# LR21_Dash.net
KiCad netlist of a schematic drawn in EAGLE
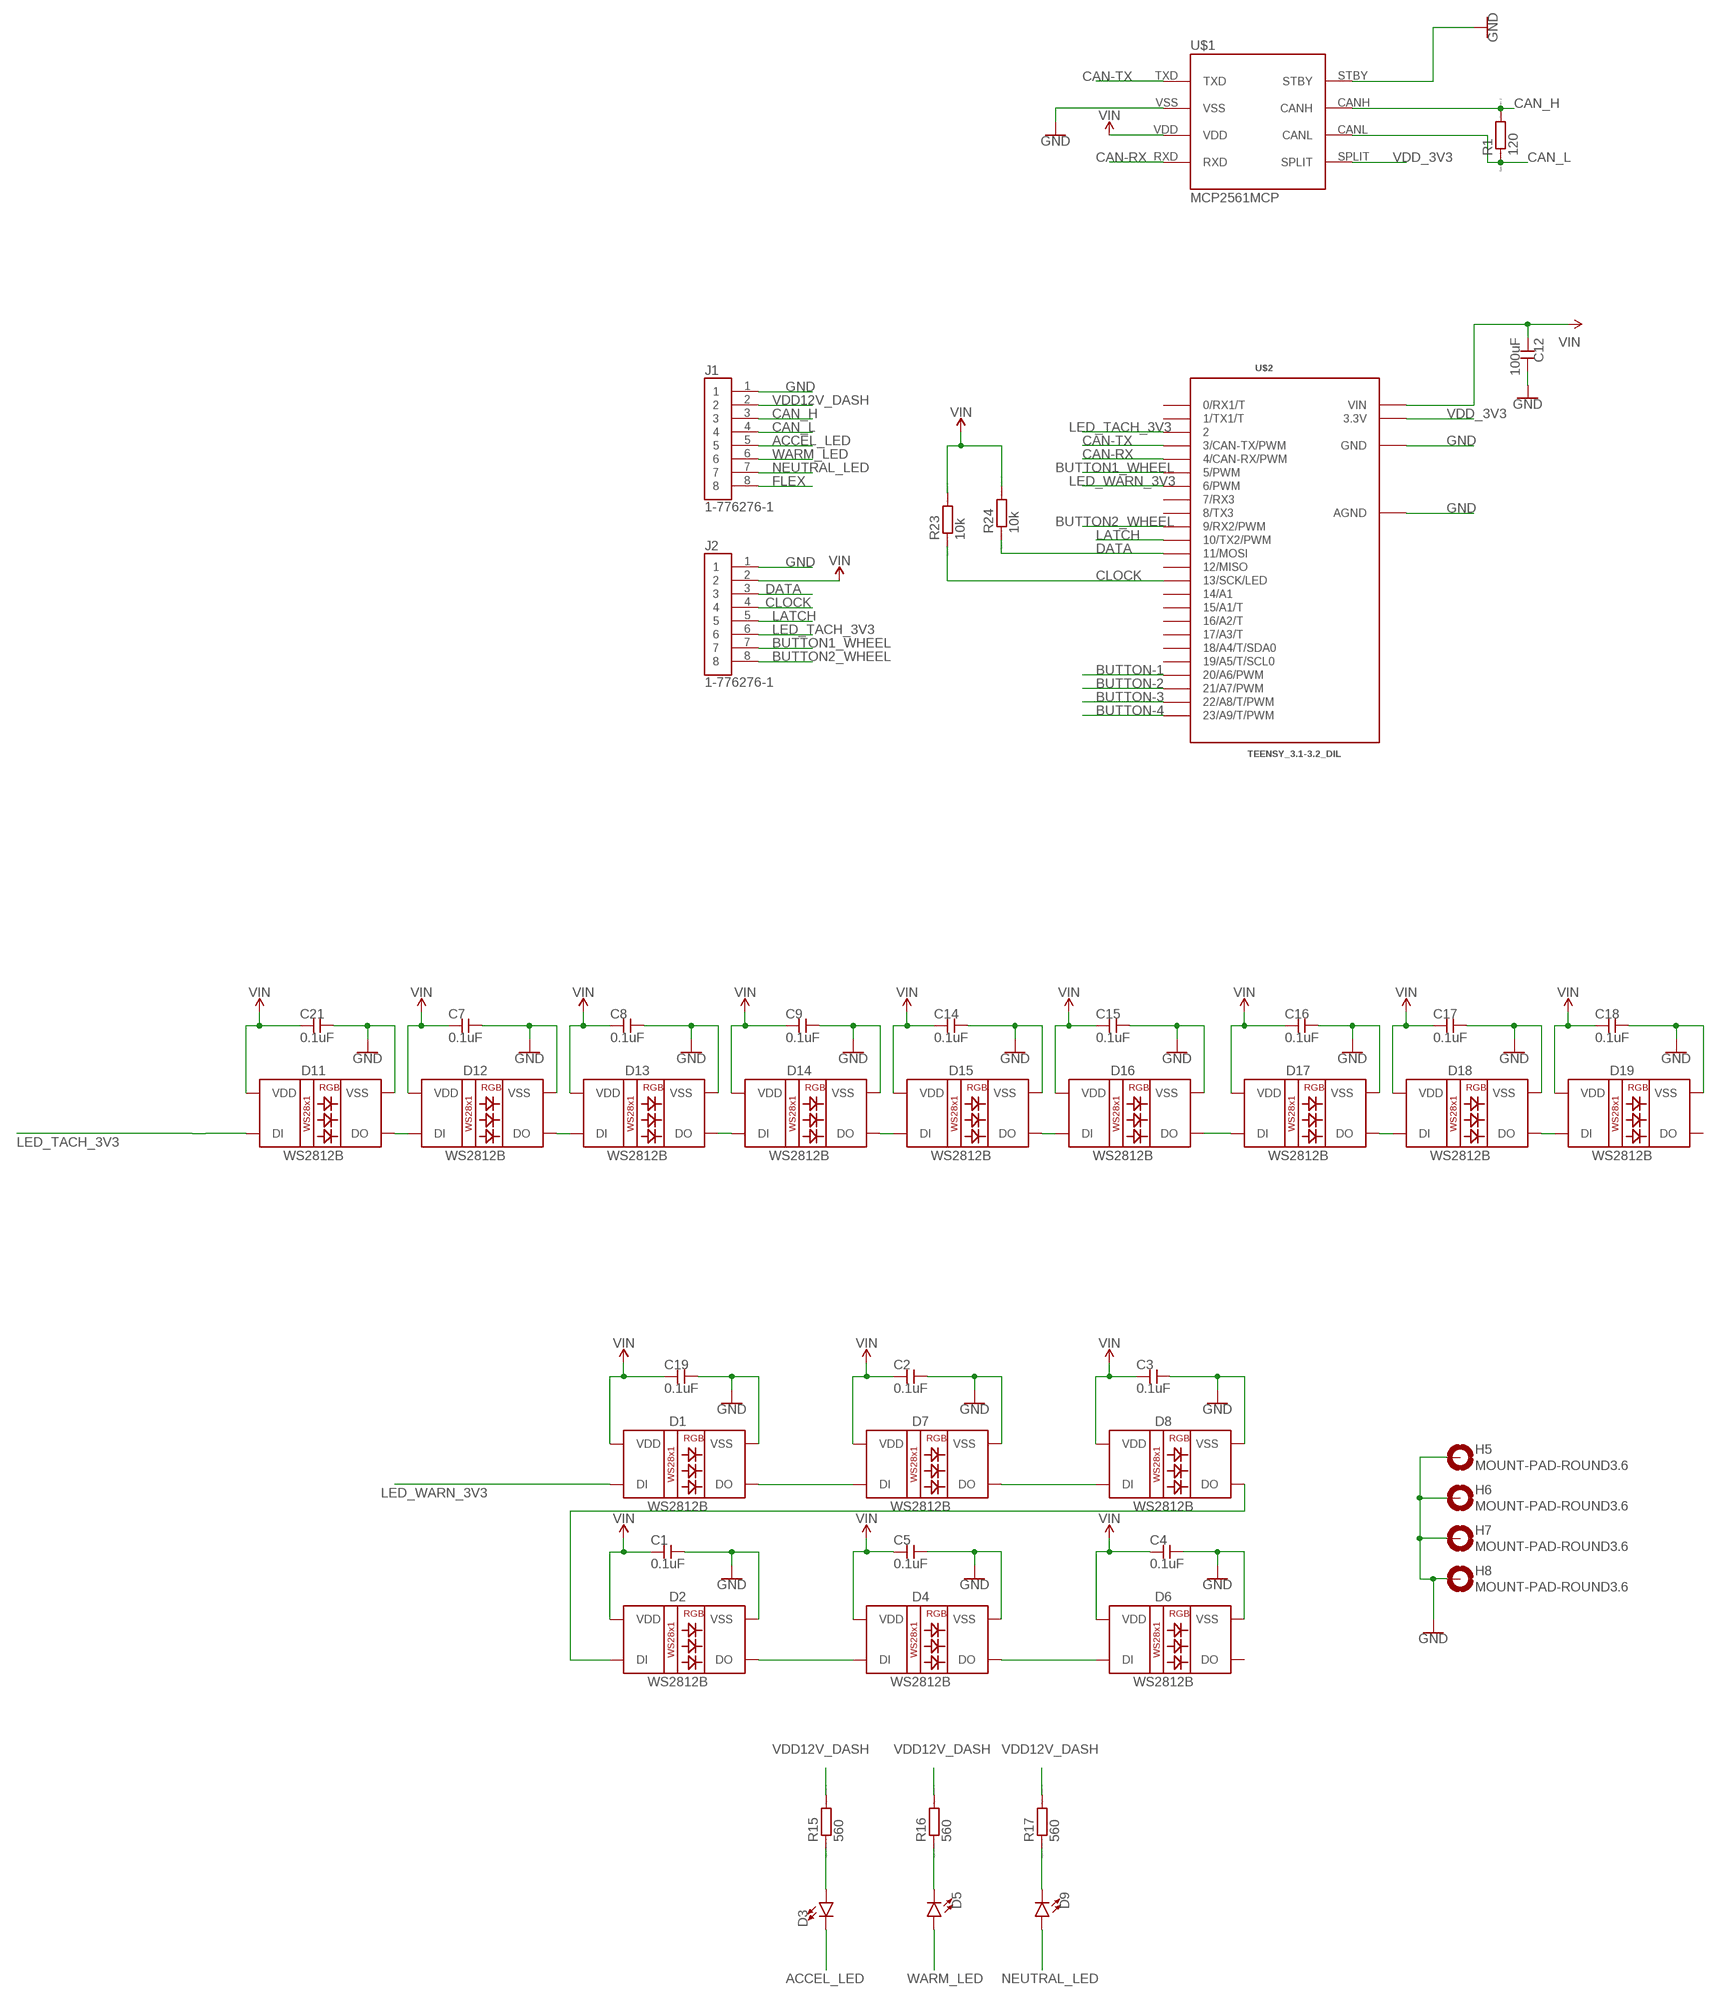
[diagram p0: schematic, sheet 1, part 1 of 2]
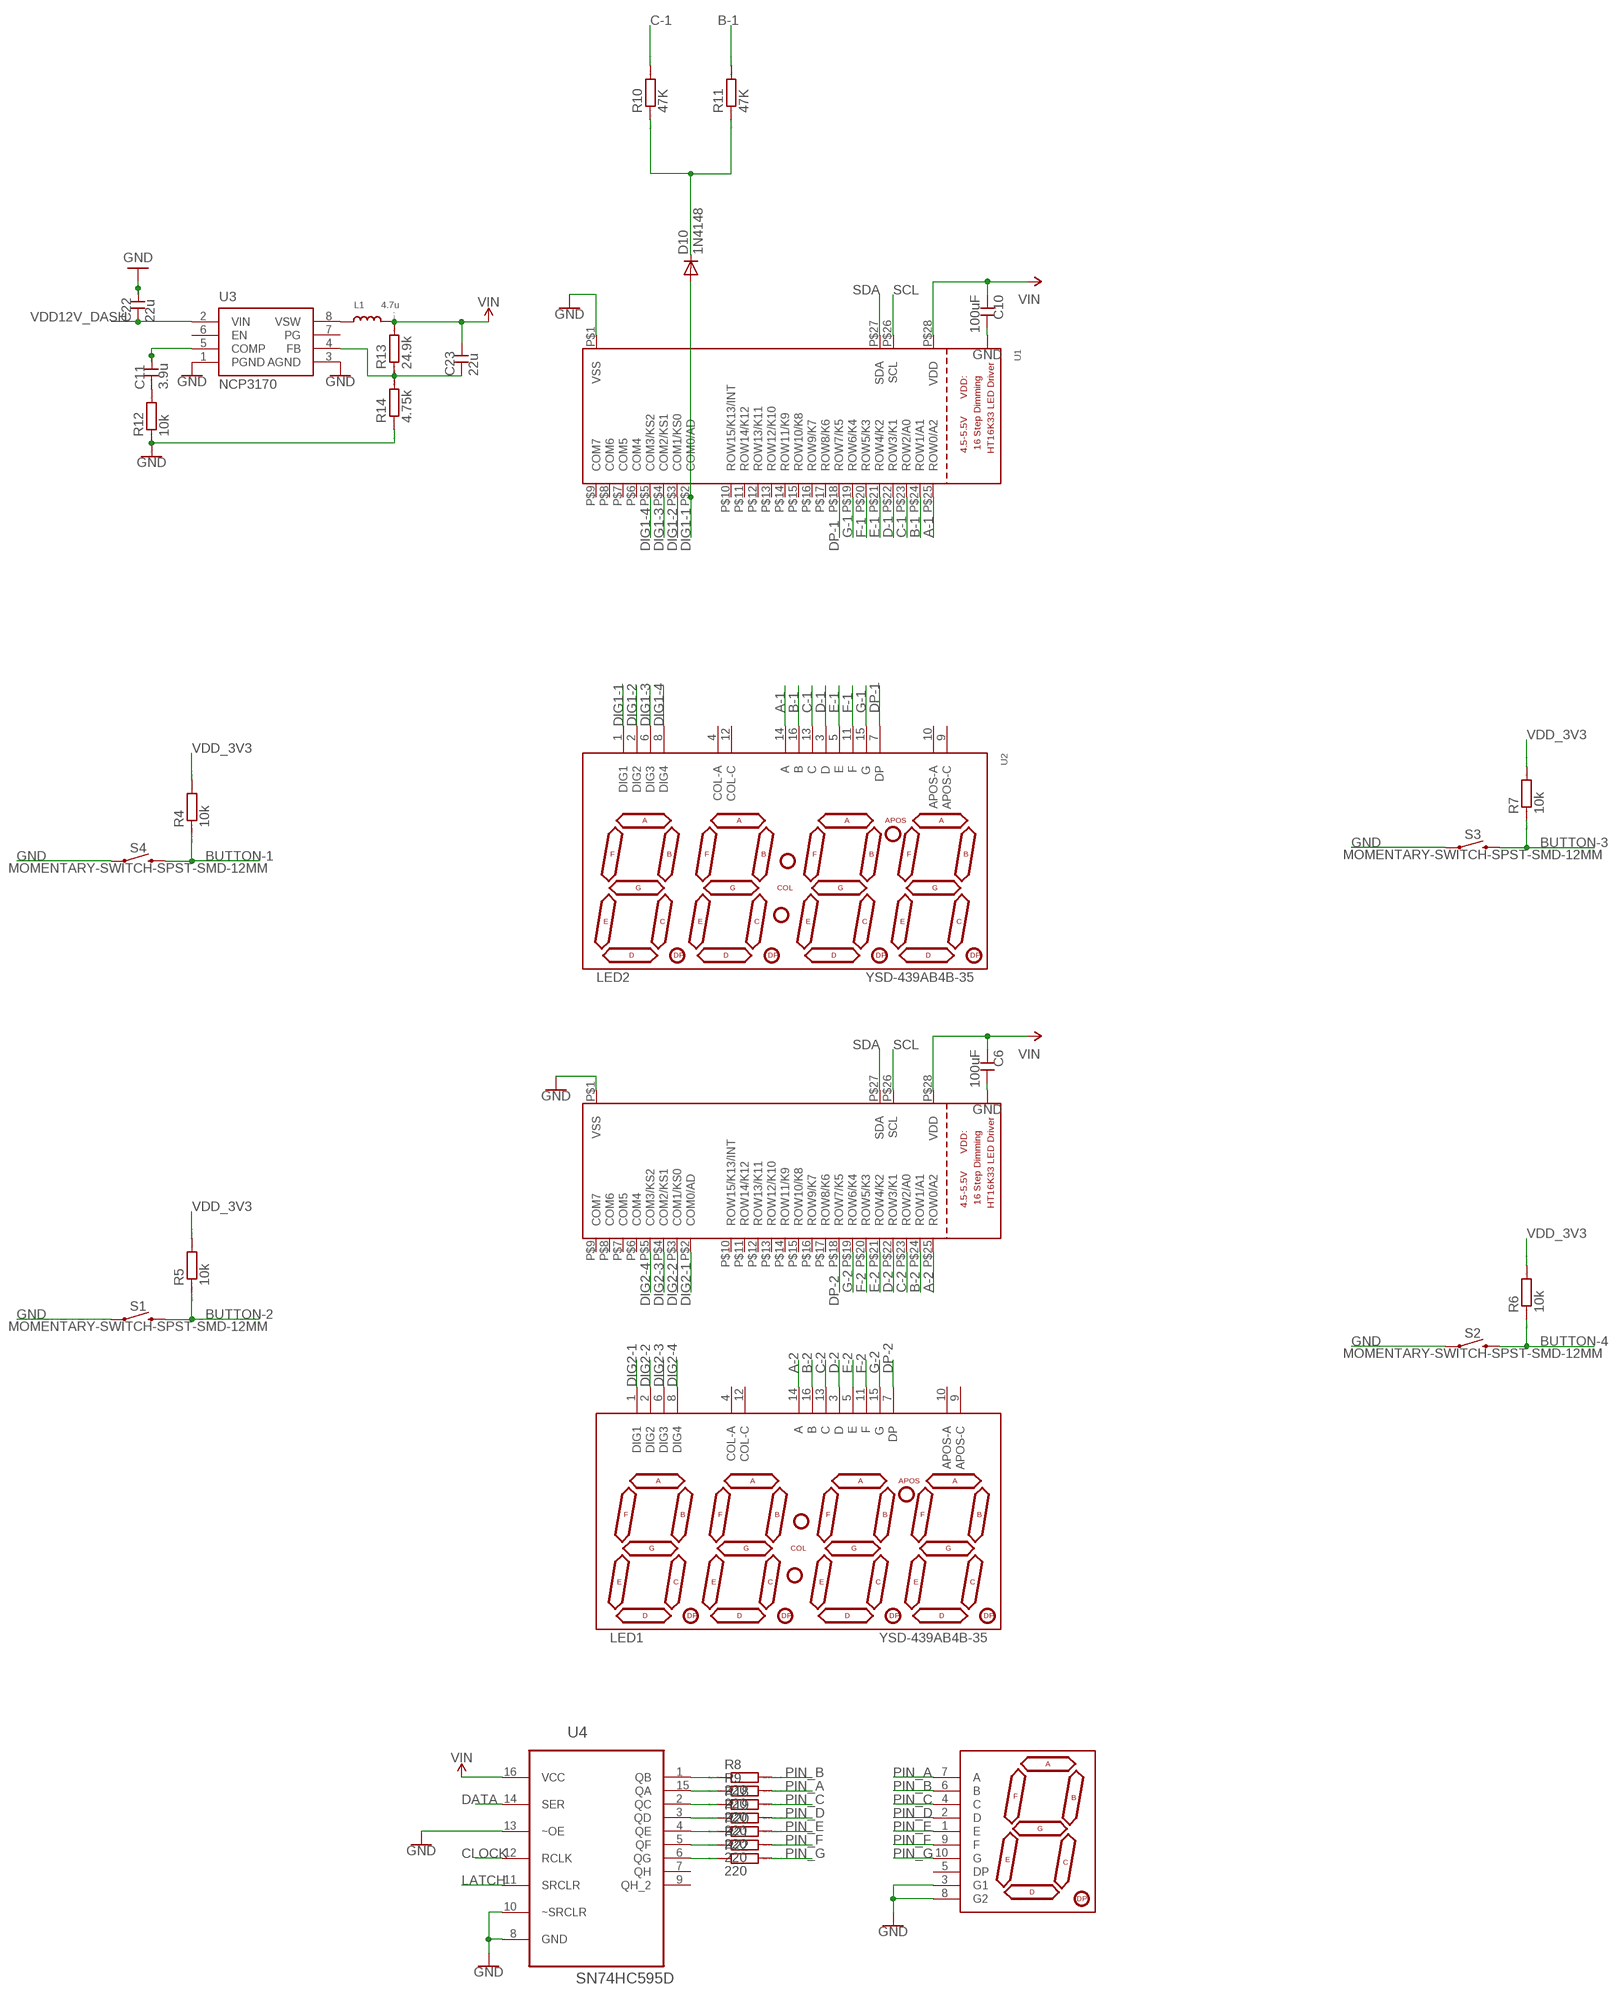
[diagram p1: schematic, sheet 1, part 2 of 2]

(export (version "E")
  (design (tool "Eeschema 10.0.6"))
  (components
    (comp (ref "C1")
      (value "0.1uF")
      (footprint "eagle-import:1005")
      (libsource (lib "eagle-import") (part "CAP-1005"))
    )
    (comp (ref "C2")
      (value "0.1uF")
      (footprint "eagle-import:1005")
      (libsource (lib "eagle-import") (part "CAP-1005"))
    )
    (comp (ref "C3")
      (value "0.1uF")
      (footprint "eagle-import:1005")
      (libsource (lib "eagle-import") (part "CAP-1005"))
    )
    (comp (ref "C4")
      (value "0.1uF")
      (footprint "eagle-import:1005")
      (libsource (lib "eagle-import") (part "CAP-1005"))
    )
    (comp (ref "C5")
      (value "0.1uF")
      (footprint "eagle-import:1005")
      (libsource (lib "eagle-import") (part "CAP-1005"))
    )
    (comp (ref "C6")
      (value "100uF")
      (footprint "eagle-import:1005")
      (libsource (lib "eagle-import") (part "CAP-1005"))
    )
    (comp (ref "C7")
      (value "0.1uF")
      (footprint "eagle-import:1005")
      (libsource (lib "eagle-import") (part "CAP-1005"))
    )
    (comp (ref "C8")
      (value "0.1uF")
      (footprint "eagle-import:1005")
      (libsource (lib "eagle-import") (part "CAP-1005"))
    )
    (comp (ref "C9")
      (value "0.1uF")
      (footprint "eagle-import:1005")
      (libsource (lib "eagle-import") (part "CAP-1005"))
    )
    (comp (ref "C10")
      (value "100uF")
      (footprint "eagle-import:1005")
      (libsource (lib "eagle-import") (part "CAP-1005"))
    )
    (comp (ref "C11")
      (value "3.9u")
      (footprint "eagle-import:1005")
      (libsource (lib "eagle-import") (part "CAP-1005"))
    )
    (comp (ref "C12")
      (value "100uF")
      (footprint "eagle-import:1005")
      (libsource (lib "eagle-import") (part "CAP-1005"))
    )
    (comp (ref "C14")
      (value "0.1uF")
      (footprint "eagle-import:1005")
      (libsource (lib "eagle-import") (part "CAP-1005"))
    )
    (comp (ref "C15")
      (value "0.1uF")
      (footprint "eagle-import:1005")
      (libsource (lib "eagle-import") (part "CAP-1005"))
    )
    (comp (ref "C16")
      (value "0.1uF")
      (footprint "eagle-import:1005")
      (libsource (lib "eagle-import") (part "CAP-1005"))
    )
    (comp (ref "C17")
      (value "0.1uF")
      (footprint "eagle-import:1005")
      (libsource (lib "eagle-import") (part "CAP-1005"))
    )
    (comp (ref "C18")
      (value "0.1uF")
      (footprint "eagle-import:1005")
      (libsource (lib "eagle-import") (part "CAP-1005"))
    )
    (comp (ref "C19")
      (value "0.1uF")
      (footprint "eagle-import:1005")
      (libsource (lib "eagle-import") (part "CAP-1005"))
    )
    (comp (ref "C21")
      (value "0.1uF")
      (footprint "eagle-import:1005")
      (libsource (lib "eagle-import") (part "CAP-1005"))
    )
    (comp (ref "C22")
      (value "22u")
      (footprint "eagle-import:1005")
      (libsource (lib "eagle-import") (part "CAP-1005"))
    )
    (comp (ref "C23")
      (value "22u")
      (footprint "eagle-import:1005")
      (libsource (lib "eagle-import") (part "CAP-1005"))
    )
    (comp (ref "D1")
      (value "WS2812B")
      (footprint "eagle-import:WS2812B")
      (libsource (lib "eagle-import") (part "WS2812B"))
    )
    (comp (ref "D2")
      (value "WS2812B")
      (footprint "eagle-import:WS2812B")
      (libsource (lib "eagle-import") (part "WS2812B"))
    )
    (comp (ref "D3")
      (value "LED5MM")
      (footprint "eagle-import:LED_5MM")
      (libsource (lib "eagle-import") (part "LED5MM"))
    )
    (comp (ref "D4")
      (value "WS2812B")
      (footprint "eagle-import:WS2812B")
      (libsource (lib "eagle-import") (part "WS2812B"))
    )
    (comp (ref "D5")
      (value "LED5MM")
      (footprint "eagle-import:LED_5MM")
      (libsource (lib "eagle-import") (part "LED5MM"))
    )
    (comp (ref "D6")
      (value "WS2812B")
      (footprint "eagle-import:WS2812B")
      (libsource (lib "eagle-import") (part "WS2812B"))
    )
    (comp (ref "D7")
      (value "WS2812B")
      (footprint "eagle-import:WS2812B")
      (libsource (lib "eagle-import") (part "WS2812B"))
    )
    (comp (ref "D8")
      (value "WS2812B")
      (footprint "eagle-import:WS2812B")
      (libsource (lib "eagle-import") (part "WS2812B"))
    )
    (comp (ref "D9")
      (value "LED5MM")
      (footprint "eagle-import:LED_5MM")
      (libsource (lib "eagle-import") (part "LED5MM"))
    )
    (comp (ref "D10")
      (value "1N4148")
      (footprint "eagle-import:DO35-10")
      (libsource (lib "eagle-import") (part "1N4148"))
    )
    (comp (ref "D11")
      (value "WS2812B")
      (footprint "eagle-import:WS2812B")
      (libsource (lib "eagle-import") (part "WS2812B"))
    )
    (comp (ref "D12")
      (value "WS2812B")
      (footprint "eagle-import:WS2812B")
      (libsource (lib "eagle-import") (part "WS2812B"))
    )
    (comp (ref "D13")
      (value "WS2812B")
      (footprint "eagle-import:WS2812B")
      (libsource (lib "eagle-import") (part "WS2812B"))
    )
    (comp (ref "D14")
      (value "WS2812B")
      (footprint "eagle-import:WS2812B")
      (libsource (lib "eagle-import") (part "WS2812B"))
    )
    (comp (ref "D15")
      (value "WS2812B")
      (footprint "eagle-import:WS2812B")
      (libsource (lib "eagle-import") (part "WS2812B"))
    )
    (comp (ref "D16")
      (value "WS2812B")
      (footprint "eagle-import:WS2812B")
      (libsource (lib "eagle-import") (part "WS2812B"))
    )
    (comp (ref "D17")
      (value "WS2812B")
      (footprint "eagle-import:WS2812B")
      (libsource (lib "eagle-import") (part "WS2812B"))
    )
    (comp (ref "D18")
      (value "WS2812B")
      (footprint "eagle-import:WS2812B")
      (libsource (lib "eagle-import") (part "WS2812B"))
    )
    (comp (ref "D19")
      (value "WS2812B")
      (footprint "eagle-import:WS2812B")
      (libsource (lib "eagle-import") (part "WS2812B"))
    )
    (comp (ref "H5")
      (value "MOUNT-PAD-ROUND3.6")
      (footprint "eagle-import:3,6-PAD")
      (libsource (lib "eagle-import") (part "MOUNT-PAD-ROUND3.6"))
    )
    (comp (ref "H6")
      (value "MOUNT-PAD-ROUND3.6")
      (footprint "eagle-import:3,6-PAD")
      (libsource (lib "eagle-import") (part "MOUNT-PAD-ROUND3.6"))
    )
    (comp (ref "H7")
      (value "MOUNT-PAD-ROUND3.6")
      (footprint "eagle-import:3,6-PAD")
      (libsource (lib "eagle-import") (part "MOUNT-PAD-ROUND3.6"))
    )
    (comp (ref "H8")
      (value "MOUNT-PAD-ROUND3.6")
      (footprint "eagle-import:3,6-PAD")
      (libsource (lib "eagle-import") (part "MOUNT-PAD-ROUND3.6"))
    )
    (comp (ref "J1")
      (value "1-776276-1")
      (footprint "eagle-import:TE_1-776276-1")
      (fields (field (name "MANUFACTURER") "TE Connectivity"))
      (libsource (lib "eagle-import") (part "1-776276-1"))
    )
    (comp (ref "J2")
      (value "1-776276-1")
      (footprint "eagle-import:TE_1-776276-1")
      (fields (field (name "MANUFACTURER") "TE Connectivity"))
      (libsource (lib "eagle-import") (part "1-776276-1"))
    )
    (comp (ref "L1")
      (value "4.7u")
      (footprint "eagle-import:INDUCTOR_1007")
      (libsource (lib "eagle-import") (part "INDUCTOR"))
    )
    (comp (ref "LED1")
      (value "YSD-439AB4B-35")
      (footprint "eagle-import:7-SEGMENT-4DIGIT-YOUNGSUN")
      (libsource (lib "eagle-import") (part "7-SEGMENT-4DIGIT-10MM-BLUE"))
    )
    (comp (ref "LED2")
      (value "YSD-439AB4B-35")
      (footprint "eagle-import:7-SEGMENT-4DIGIT-YOUNGSUN")
      (libsource (lib "eagle-import") (part "7-SEGMENT-4DIGIT-10MM-BLUE"))
    )
    (comp (ref "R1")
      (value "120")
      (footprint "eagle-import:R0805")
      (libsource (lib "eagle-import") (part "R"))
    )
    (comp (ref "R4")
      (value "10k")
      (footprint "eagle-import:R0805")
      (libsource (lib "eagle-import") (part "R"))
    )
    (comp (ref "R5")
      (value "10k")
      (footprint "eagle-import:R0805")
      (libsource (lib "eagle-import") (part "R"))
    )
    (comp (ref "R6")
      (value "10k")
      (footprint "eagle-import:R0805")
      (libsource (lib "eagle-import") (part "R"))
    )
    (comp (ref "R7")
      (value "10k")
      (footprint "eagle-import:R0805")
      (libsource (lib "eagle-import") (part "R"))
    )
    (comp (ref "R8")
      (value "220")
      (footprint "eagle-import:R0805")
      (libsource (lib "eagle-import") (part "R"))
    )
    (comp (ref "R9")
      (value "220")
      (footprint "eagle-import:R0805")
      (libsource (lib "eagle-import") (part "R"))
    )
    (comp (ref "R10")
      (value "47K")
      (footprint "eagle-import:R0805")
      (libsource (lib "eagle-import") (part "R"))
    )
    (comp (ref "R11")
      (value "47K")
      (footprint "eagle-import:R0805")
      (libsource (lib "eagle-import") (part "R"))
    )
    (comp (ref "R12")
      (value "10k")
      (footprint "eagle-import:R0805")
      (libsource (lib "eagle-import") (part "R"))
    )
    (comp (ref "R13")
      (value "24.9k")
      (footprint "eagle-import:R0805")
      (libsource (lib "eagle-import") (part "R"))
    )
    (comp (ref "R14")
      (value "4.75k")
      (footprint "eagle-import:R0805")
      (libsource (lib "eagle-import") (part "R"))
    )
    (comp (ref "R15")
      (value "560")
      (footprint "eagle-import:R0805")
      (libsource (lib "eagle-import") (part "R"))
    )
    (comp (ref "R16")
      (value "560")
      (footprint "eagle-import:R0805")
      (libsource (lib "eagle-import") (part "R"))
    )
    (comp (ref "R17")
      (value "560")
      (footprint "eagle-import:R0805")
      (libsource (lib "eagle-import") (part "R"))
    )
    (comp (ref "R18")
      (value "220")
      (footprint "eagle-import:R0805")
      (libsource (lib "eagle-import") (part "R"))
    )
    (comp (ref "R19")
      (value "220")
      (footprint "eagle-import:R0805")
      (libsource (lib "eagle-import") (part "R"))
    )
    (comp (ref "R20")
      (value "220")
      (footprint "eagle-import:R0805")
      (libsource (lib "eagle-import") (part "R"))
    )
    (comp (ref "R21")
      (value "220")
      (footprint "eagle-import:R0805")
      (libsource (lib "eagle-import") (part "R"))
    )
    (comp (ref "R22")
      (value "220")
      (footprint "eagle-import:R0805")
      (libsource (lib "eagle-import") (part "R"))
    )
    (comp (ref "R23")
      (value "10k")
      (footprint "eagle-import:R0805")
      (libsource (lib "eagle-import") (part "R"))
    )
    (comp (ref "R24")
      (value "10k")
      (footprint "eagle-import:R0805")
      (libsource (lib "eagle-import") (part "R"))
    )
    (comp (ref "S1")
      (value "MOMENTARY-SWITCH-SPST-SMD-12MM")
      (footprint "eagle-import:TACTILE_SWITCH_SMD_12MM")
      (libsource (lib "eagle-import") (part "MOMENTARY-SWITCH-SPST-SMD-12MM"))
    )
    (comp (ref "S2")
      (value "MOMENTARY-SWITCH-SPST-SMD-12MM")
      (footprint "eagle-import:TACTILE_SWITCH_SMD_12MM")
      (libsource (lib "eagle-import") (part "MOMENTARY-SWITCH-SPST-SMD-12MM"))
    )
    (comp (ref "S3")
      (value "MOMENTARY-SWITCH-SPST-SMD-12MM")
      (footprint "eagle-import:TACTILE_SWITCH_SMD_12MM")
      (libsource (lib "eagle-import") (part "MOMENTARY-SWITCH-SPST-SMD-12MM"))
    )
    (comp (ref "S4")
      (value "MOMENTARY-SWITCH-SPST-SMD-12MM")
      (footprint "eagle-import:TACTILE_SWITCH_SMD_12MM")
      (libsource (lib "eagle-import") (part "MOMENTARY-SWITCH-SPST-SMD-12MM"))
    )
    (comp (ref "U$1")
      (value "MCP2561MCP")
      (footprint "eagle-import:MCP2561_PDIP")
      (libsource (lib "eagle-import") (part "MCP2561MCP"))
    )
    (comp (ref "U$2")
      (value "TEENSY_3.1-3.2_DIL")
      (footprint "eagle-import:TEENSY_3.0-3.2&LC_DIL")
      (libsource (lib "eagle-import") (part "TEENSY_3.1-3.2_DIL"))
    )
    (comp (ref "U$3")
      (value "YSD-160AB3C-8")
      (footprint "eagle-import:7-SEGMENT-1_PTH")
      (libsource (lib "eagle-import") (part "7-SEGMENT-1DIGIT-1INCH-BLUE"))
    )
    (comp (ref "U1")
      (value "HT16K33_SOP28")
      (footprint "eagle-import:SOP28_300MIL")
      (libsource (lib "eagle-import") (part "HT16K33_SOP28"))
    )
    (comp (ref "U2")
      (value "HT16K33_SOP28")
      (footprint "eagle-import:SOP28_300MIL")
      (libsource (lib "eagle-import") (part "HT16K33_SOP28"))
    )
    (comp (ref "U3")
      (value "NCP3170")
      (footprint "eagle-import:SOIC8")
      (fields (field (name "MF") "ON Semiconductor"))
      (libsource (lib "eagle-import") (part "NCP3170"))
    )
    (comp (ref "U4")
      (value "SN74HC595D")
      (footprint "eagle-import:SOIC127P600X175-16N")
      (fields (field (name "DIGI-KEY_PART_NUMBER") "296-8344-5-ND") (field (name "MF") "Texas Instruments"))
      (libsource (lib "eagle-import") (part "SN74HC595D"))
    )
  )
  (nets
    (net (code "1") (name "/A-1") (class "Default")
      (node (ref "LED2") (pin "14") (pinfunction "A_14") (pintype "bidirectional"))
      (node (ref "U1") (pin "P$25") (pinfunction "ROW0/A2_P$25") (pintype "bidirectional"))
    )
    (net (code "2") (name "/A-2") (class "Default")
      (node (ref "LED1") (pin "14") (pinfunction "A_14") (pintype "bidirectional"))
      (node (ref "U2") (pin "P$25") (pinfunction "ROW0/A2_P$25") (pintype "bidirectional"))
    )
    (net (code "3") (name "/ACCEL_LED") (class "Default")
      (node (ref "D3") (pin "K") (pinfunction "C_K") (pintype "passive"))
      (node (ref "J1") (pin "5") (pinfunction "5_5") (pintype "passive"))
    )
    (net (code "4") (name "/B-1") (class "Default")
      (node (ref "LED2") (pin "16") (pinfunction "B_16") (pintype "bidirectional"))
      (node (ref "R11") (pin "2") (pinfunction "2_2") (pintype "passive"))
      (node (ref "U1") (pin "P$24") (pinfunction "ROW1/A1_P$24") (pintype "bidirectional"))
    )
    (net (code "5") (name "/B-2") (class "Default")
      (node (ref "LED1") (pin "16") (pinfunction "B_16") (pintype "bidirectional"))
      (node (ref "U2") (pin "P$24") (pinfunction "ROW1/A1_P$24") (pintype "bidirectional"))
    )
    (net (code "6") (name "/BUTTON-1") (class "Default")
      (node (ref "R4") (pin "1") (pinfunction "1_1") (pintype "passive"))
      (node (ref "S4") (pin "3") (pinfunction "2_3") (pintype "passive"))
      (node (ref "U$2") (pin "20/A6") (pinfunction "20/A6/PWM_20/A6") (pintype "bidirectional"))
    )
    (net (code "7") (name "/BUTTON-2") (class "Default")
      (node (ref "R5") (pin "1") (pinfunction "1_1") (pintype "passive"))
      (node (ref "S1") (pin "3") (pinfunction "2_3") (pintype "passive"))
      (node (ref "U$2") (pin "21/A7") (pinfunction "21/A7/PWM_21/A7") (pintype "bidirectional"))
    )
    (net (code "8") (name "/BUTTON-3") (class "Default")
      (node (ref "R7") (pin "1") (pinfunction "1_1") (pintype "passive"))
      (node (ref "S3") (pin "3") (pinfunction "2_3") (pintype "passive"))
      (node (ref "U$2") (pin "22/A8") (pinfunction "22/A8/T/PWM_22/A8") (pintype "bidirectional"))
    )
    (net (code "9") (name "/BUTTON-4") (class "Default")
      (node (ref "R6") (pin "1") (pinfunction "1_1") (pintype "passive"))
      (node (ref "S2") (pin "3") (pinfunction "2_3") (pintype "passive"))
      (node (ref "U$2") (pin "23/A9") (pinfunction "23/A9/T/PWM_23/A9") (pintype "bidirectional"))
    )
    (net (code "10") (name "/BUTTON1_WHEEL") (class "Default")
      (node (ref "J2") (pin "7") (pinfunction "7_7") (pintype "passive"))
      (node (ref "U$2") (pin "5") (pinfunction "5/PWM_5") (pintype "bidirectional"))
    )
    (net (code "11") (name "/BUTTON2_WHEEL") (class "Default")
      (node (ref "J2") (pin "8") (pinfunction "8_8") (pintype "passive"))
      (node (ref "U$2") (pin "9") (pinfunction "9/RX2/PWM_9") (pintype "bidirectional"))
    )
    (net (code "12") (name "/C-1") (class "Default")
      (node (ref "LED2") (pin "13") (pinfunction "C_13") (pintype "bidirectional"))
      (node (ref "R10") (pin "2") (pinfunction "2_2") (pintype "passive"))
      (node (ref "U1") (pin "P$23") (pinfunction "ROW2/A0_P$23") (pintype "bidirectional"))
    )
    (net (code "13") (name "/C-2") (class "Default")
      (node (ref "LED1") (pin "13") (pinfunction "C_13") (pintype "bidirectional"))
      (node (ref "U2") (pin "P$23") (pinfunction "ROW2/A0_P$23") (pintype "bidirectional"))
    )
    (net (code "14") (name "/CAN-RX") (class "Default")
      (node (ref "U$1") (pin "RXD") (pinfunction "RXD_RXD") (pintype "bidirectional"))
      (node (ref "U$2") (pin "4") (pinfunction "4/CAN-RX/PWM_4") (pintype "bidirectional"))
    )
    (net (code "15") (name "/CAN-TX") (class "Default")
      (node (ref "U$1") (pin "TXD") (pinfunction "TXD_TXD") (pintype "bidirectional"))
      (node (ref "U$2") (pin "3") (pinfunction "3/CAN-TX/PWM_3") (pintype "bidirectional"))
    )
    (net (code "16") (name "/CAN_H") (class "Default")
      (node (ref "J1") (pin "3") (pinfunction "3_3") (pintype "passive"))
      (node (ref "R1") (pin "2") (pinfunction "2_2") (pintype "passive"))
      (node (ref "U$1") (pin "CANH") (pinfunction "CANH_CANH") (pintype "bidirectional"))
    )
    (net (code "17") (name "/CAN_L") (class "Default")
      (node (ref "J1") (pin "4") (pinfunction "4_4") (pintype "passive"))
      (node (ref "R1") (pin "1") (pinfunction "1_1") (pintype "passive"))
      (node (ref "U$1") (pin "CANL") (pinfunction "CANL_CANL") (pintype "bidirectional"))
    )
    (net (code "18") (name "/CLOCK") (class "Default")
      (node (ref "J2") (pin "4") (pinfunction "4_4") (pintype "passive"))
      (node (ref "R23") (pin "1") (pinfunction "1_1") (pintype "passive"))
      (node (ref "U$2") (pin "13") (pinfunction "13/SCK/LED_13") (pintype "bidirectional"))
      (node (ref "U4") (pin "12") (pinfunction "RCLK_12") (pintype "input"))
    )
    (net (code "19") (name "/D-1") (class "Default")
      (node (ref "LED2") (pin "3") (pinfunction "D_3") (pintype "bidirectional"))
      (node (ref "U1") (pin "P$22") (pinfunction "ROW3/K1_P$22") (pintype "bidirectional"))
    )
    (net (code "20") (name "/D-2") (class "Default")
      (node (ref "LED1") (pin "3") (pinfunction "D_3") (pintype "bidirectional"))
      (node (ref "U2") (pin "P$22") (pinfunction "ROW3/K1_P$22") (pintype "bidirectional"))
    )
    (net (code "21") (name "/DATA") (class "Default")
      (node (ref "J2") (pin "3") (pinfunction "3_3") (pintype "passive"))
      (node (ref "R24") (pin "1") (pinfunction "1_1") (pintype "passive"))
      (node (ref "U$2") (pin "11") (pinfunction "11/MOSI_11") (pintype "bidirectional"))
      (node (ref "U4") (pin "14") (pinfunction "SER_14") (pintype "input"))
    )
    (net (code "22") (name "/DIG1-1") (class "Default")
      (node (ref "D10") (pin "A") (pinfunction "A_A") (pintype "passive"))
      (node (ref "LED2") (pin "1") (pinfunction "DIG1_1") (pintype "bidirectional"))
      (node (ref "U1") (pin "P$2") (pinfunction "COM0/AD_P$2") (pintype "bidirectional"))
    )
    (net (code "23") (name "/DIG1-2") (class "Default")
      (node (ref "LED2") (pin "2") (pinfunction "DIG2_2") (pintype "bidirectional"))
      (node (ref "U1") (pin "P$3") (pinfunction "COM1/KS0_P$3") (pintype "bidirectional"))
    )
    (net (code "24") (name "/DIG1-3") (class "Default")
      (node (ref "LED2") (pin "6") (pinfunction "DIG3_6") (pintype "bidirectional"))
      (node (ref "U1") (pin "P$4") (pinfunction "COM2/KS1_P$4") (pintype "bidirectional"))
    )
    (net (code "25") (name "/DIG1-4") (class "Default")
      (node (ref "LED2") (pin "8") (pinfunction "DIG4_8") (pintype "bidirectional"))
      (node (ref "U1") (pin "P$5") (pinfunction "COM3/KS2_P$5") (pintype "bidirectional"))
    )
    (net (code "26") (name "/DIG2-1") (class "Default")
      (node (ref "LED1") (pin "1") (pinfunction "DIG1_1") (pintype "bidirectional"))
      (node (ref "U2") (pin "P$2") (pinfunction "COM0/AD_P$2") (pintype "bidirectional"))
    )
    (net (code "27") (name "/DIG2-2") (class "Default")
      (node (ref "LED1") (pin "2") (pinfunction "DIG2_2") (pintype "bidirectional"))
      (node (ref "U2") (pin "P$3") (pinfunction "COM1/KS0_P$3") (pintype "bidirectional"))
    )
    (net (code "28") (name "/DIG2-3") (class "Default")
      (node (ref "LED1") (pin "6") (pinfunction "DIG3_6") (pintype "bidirectional"))
      (node (ref "U2") (pin "P$4") (pinfunction "COM2/KS1_P$4") (pintype "bidirectional"))
    )
    (net (code "29") (name "/DIG2-4") (class "Default")
      (node (ref "LED1") (pin "8") (pinfunction "DIG4_8") (pintype "bidirectional"))
      (node (ref "U2") (pin "P$5") (pinfunction "COM3/KS2_P$5") (pintype "bidirectional"))
    )
    (net (code "30") (name "/DP-1") (class "Default")
      (node (ref "LED2") (pin "7") (pinfunction "DP_7") (pintype "bidirectional"))
      (node (ref "U1") (pin "P$18") (pinfunction "ROW7/K5_P$18") (pintype "bidirectional"))
    )
    (net (code "31") (name "/DP-2") (class "Default")
      (node (ref "LED1") (pin "7") (pinfunction "DP_7") (pintype "bidirectional"))
      (node (ref "U2") (pin "P$18") (pinfunction "ROW7/K5_P$18") (pintype "bidirectional"))
    )
    (net (code "32") (name "/E-1") (class "Default")
      (node (ref "LED2") (pin "5") (pinfunction "E_5") (pintype "bidirectional"))
      (node (ref "U1") (pin "P$21") (pinfunction "ROW4/K2_P$21") (pintype "bidirectional"))
    )
    (net (code "33") (name "/E-2") (class "Default")
      (node (ref "LED1") (pin "5") (pinfunction "E_5") (pintype "bidirectional"))
      (node (ref "U2") (pin "P$21") (pinfunction "ROW4/K2_P$21") (pintype "bidirectional"))
    )
    (net (code "34") (name "/F-1") (class "Default")
      (node (ref "LED2") (pin "11") (pinfunction "F_11") (pintype "bidirectional"))
      (node (ref "U1") (pin "P$20") (pinfunction "ROW5/K3_P$20") (pintype "bidirectional"))
    )
    (net (code "35") (name "/F-2") (class "Default")
      (node (ref "LED1") (pin "11") (pinfunction "F_11") (pintype "bidirectional"))
      (node (ref "U2") (pin "P$20") (pinfunction "ROW5/K3_P$20") (pintype "bidirectional"))
    )
    (net (code "36") (name "/FLEX") (class "Default")
      (node (ref "J1") (pin "8") (pinfunction "8_8") (pintype "passive"))
    )
    (net (code "37") (name "/G-1") (class "Default")
      (node (ref "LED2") (pin "15") (pinfunction "G_15") (pintype "bidirectional"))
      (node (ref "U1") (pin "P$19") (pinfunction "ROW6/K4_P$19") (pintype "bidirectional"))
    )
    (net (code "38") (name "/G-2") (class "Default")
      (node (ref "LED1") (pin "15") (pinfunction "G_15") (pintype "bidirectional"))
      (node (ref "U2") (pin "P$19") (pinfunction "ROW6/K4_P$19") (pintype "bidirectional"))
    )
    (net (code "39") (name "/LATCH") (class "Default")
      (node (ref "J2") (pin "5") (pinfunction "5_5") (pintype "passive"))
      (node (ref "U$2") (pin "10") (pinfunction "10/TX2/PWM_10") (pintype "bidirectional"))
      (node (ref "U4") (pin "11") (pinfunction "SRCLR_11") (pintype "input"))
    )
    (net (code "40") (name "/LED_TACH_3V3") (class "Default")
      (node (ref "D11") (pin "4") (pinfunction "DI_4") (pintype "bidirectional"))
      (node (ref "J2") (pin "6") (pinfunction "6_6") (pintype "passive"))
      (node (ref "U$2") (pin "2") (pinfunction "2_2") (pintype "bidirectional"))
    )
    (net (code "41") (name "/LED_WARN_3V3") (class "Default")
      (node (ref "D1") (pin "4") (pinfunction "DI_4") (pintype "bidirectional"))
      (node (ref "U$2") (pin "6") (pinfunction "6/PWM_6") (pintype "bidirectional"))
    )
    (net (code "42") (name "/NEUTRAL_LED") (class "Default")
      (node (ref "D9") (pin "A") (pinfunction "A_A") (pintype "passive"))
      (node (ref "J1") (pin "7") (pinfunction "7_7") (pintype "passive"))
    )
    (net (code "43") (name "/PIN_A") (class "Default")
      (node (ref "R9") (pin "2") (pinfunction "2_2") (pintype "passive"))
      (node (ref "U$3") (pin "7") (pinfunction "A_7") (pintype "bidirectional"))
    )
    (net (code "44") (name "/PIN_B") (class "Default")
      (node (ref "R8") (pin "2") (pinfunction "2_2") (pintype "passive"))
      (node (ref "U$3") (pin "6") (pinfunction "B_6") (pintype "bidirectional"))
    )
    (net (code "45") (name "/PIN_C") (class "Default")
      (node (ref "R18") (pin "2") (pinfunction "2_2") (pintype "passive"))
      (node (ref "U$3") (pin "4") (pinfunction "C_4") (pintype "bidirectional"))
    )
    (net (code "46") (name "/PIN_D") (class "Default")
      (node (ref "R19") (pin "2") (pinfunction "2_2") (pintype "passive"))
      (node (ref "U$3") (pin "2") (pinfunction "D_2") (pintype "bidirectional"))
    )
    (net (code "47") (name "/PIN_E") (class "Default")
      (node (ref "R20") (pin "2") (pinfunction "2_2") (pintype "passive"))
      (node (ref "U$3") (pin "1") (pinfunction "E_1") (pintype "bidirectional"))
    )
    (net (code "48") (name "/PIN_F") (class "Default")
      (node (ref "R21") (pin "2") (pinfunction "2_2") (pintype "passive"))
      (node (ref "U$3") (pin "9") (pinfunction "F_9") (pintype "bidirectional"))
    )
    (net (code "49") (name "/PIN_G") (class "Default")
      (node (ref "R22") (pin "2") (pinfunction "2_2") (pintype "passive"))
      (node (ref "U$3") (pin "10") (pinfunction "G_10") (pintype "bidirectional"))
    )
    (net (code "50") (name "/SCL") (class "Default")
      (node (ref "U1") (pin "P$26") (pinfunction "SCL_P$26") (pintype "bidirectional"))
      (node (ref "U2") (pin "P$26") (pinfunction "SCL_P$26") (pintype "bidirectional"))
    )
    (net (code "51") (name "/SDA") (class "Default")
      (node (ref "U1") (pin "P$27") (pinfunction "SDA_P$27") (pintype "bidirectional"))
      (node (ref "U2") (pin "P$27") (pinfunction "SDA_P$27") (pintype "bidirectional"))
    )
    (net (code "52") (name "/VDD12V_DASH") (class "Default")
      (node (ref "C22") (pin "P$1") (pinfunction "1_P$1") (pintype "passive"))
      (node (ref "J1") (pin "2") (pinfunction "2_2") (pintype "passive"))
      (node (ref "R15") (pin "2") (pinfunction "2_2") (pintype "passive"))
      (node (ref "R16") (pin "2") (pinfunction "2_2") (pintype "passive"))
      (node (ref "R17") (pin "2") (pinfunction "2_2") (pintype "passive"))
      (node (ref "U3") (pin "2") (pinfunction "VIN_2") (pintype "bidirectional"))
    )
    (net (code "53") (name "/VDD_3V3") (class "Default")
      (node (ref "R4") (pin "2") (pinfunction "2_2") (pintype "passive"))
      (node (ref "R5") (pin "2") (pinfunction "2_2") (pintype "passive"))
      (node (ref "R6") (pin "2") (pinfunction "2_2") (pintype "passive"))
      (node (ref "R7") (pin "2") (pinfunction "2_2") (pintype "passive"))
      (node (ref "U$1") (pin "SPLIT") (pinfunction "SPLIT_SPLIT") (pintype "bidirectional"))
      (node (ref "U$2") (pin "3.3V") (pinfunction "3.3V_3.3V") (pintype "power_in"))
    )
    (net (code "54") (name "/WARM_LED") (class "Default")
      (node (ref "D5") (pin "A") (pinfunction "A_A") (pintype "passive"))
      (node (ref "J1") (pin "6") (pinfunction "6_6") (pintype "passive"))
    )
    (net (code "55") (name "GND") (class "Default")
      (node (ref "C1") (pin "P$2") (pinfunction "2_P$2") (pintype "passive"))
      (node (ref "C10") (pin "P$2") (pinfunction "2_P$2") (pintype "passive"))
      (node (ref "C12") (pin "P$2") (pinfunction "2_P$2") (pintype "passive"))
      (node (ref "C14") (pin "P$2") (pinfunction "2_P$2") (pintype "passive"))
      (node (ref "C15") (pin "P$2") (pinfunction "2_P$2") (pintype "passive"))
      (node (ref "C16") (pin "P$2") (pinfunction "2_P$2") (pintype "passive"))
      (node (ref "C17") (pin "P$2") (pinfunction "2_P$2") (pintype "passive"))
      (node (ref "C18") (pin "P$2") (pinfunction "2_P$2") (pintype "passive"))
      (node (ref "C19") (pin "P$2") (pinfunction "2_P$2") (pintype "passive"))
      (node (ref "C2") (pin "P$2") (pinfunction "2_P$2") (pintype "passive"))
      (node (ref "C21") (pin "P$2") (pinfunction "2_P$2") (pintype "passive"))
      (node (ref "C22") (pin "P$2") (pinfunction "2_P$2") (pintype "passive"))
      (node (ref "C3") (pin "P$2") (pinfunction "2_P$2") (pintype "passive"))
      (node (ref "C4") (pin "P$2") (pinfunction "2_P$2") (pintype "passive"))
      (node (ref "C5") (pin "P$2") (pinfunction "2_P$2") (pintype "passive"))
      (node (ref "C6") (pin "P$2") (pinfunction "2_P$2") (pintype "passive"))
      (node (ref "C7") (pin "P$2") (pinfunction "2_P$2") (pintype "passive"))
      (node (ref "C8") (pin "P$2") (pinfunction "2_P$2") (pintype "passive"))
      (node (ref "C9") (pin "P$2") (pinfunction "2_P$2") (pintype "passive"))
      (node (ref "D1") (pin "3") (pinfunction "VSS_3") (pintype "bidirectional"))
      (node (ref "D11") (pin "3") (pinfunction "VSS_3") (pintype "bidirectional"))
      (node (ref "D12") (pin "3") (pinfunction "VSS_3") (pintype "bidirectional"))
      (node (ref "D13") (pin "3") (pinfunction "VSS_3") (pintype "bidirectional"))
      (node (ref "D14") (pin "3") (pinfunction "VSS_3") (pintype "bidirectional"))
      (node (ref "D15") (pin "3") (pinfunction "VSS_3") (pintype "bidirectional"))
      (node (ref "D16") (pin "3") (pinfunction "VSS_3") (pintype "bidirectional"))
      (node (ref "D17") (pin "3") (pinfunction "VSS_3") (pintype "bidirectional"))
      (node (ref "D18") (pin "3") (pinfunction "VSS_3") (pintype "bidirectional"))
      (node (ref "D19") (pin "3") (pinfunction "VSS_3") (pintype "bidirectional"))
      (node (ref "D2") (pin "3") (pinfunction "VSS_3") (pintype "bidirectional"))
      (node (ref "D4") (pin "3") (pinfunction "VSS_3") (pintype "bidirectional"))
      (node (ref "D6") (pin "3") (pinfunction "VSS_3") (pintype "bidirectional"))
      (node (ref "D7") (pin "3") (pinfunction "VSS_3") (pintype "bidirectional"))
      (node (ref "D8") (pin "3") (pinfunction "VSS_3") (pintype "bidirectional"))
      (node (ref "H5") (pin "B3,6") (pinfunction "MOUNT_B3,6") (pintype "passive"))
      (node (ref "H6") (pin "B3,6") (pinfunction "MOUNT_B3,6") (pintype "passive"))
      (node (ref "H7") (pin "B3,6") (pinfunction "MOUNT_B3,6") (pintype "passive"))
      (node (ref "H8") (pin "B3,6") (pinfunction "MOUNT_B3,6") (pintype "passive"))
      (node (ref "J1") (pin "1") (pinfunction "1_1") (pintype "passive"))
      (node (ref "J2") (pin "1") (pinfunction "1_1") (pintype "passive"))
      (node (ref "R12") (pin "1") (pinfunction "1_1") (pintype "passive"))
      (node (ref "R14") (pin "1") (pinfunction "1_1") (pintype "passive"))
      (node (ref "S1") (pin "1") (pinfunction "1_1") (pintype "passive"))
      (node (ref "S2") (pin "1") (pinfunction "1_1") (pintype "passive"))
      (node (ref "S3") (pin "1") (pinfunction "1_1") (pintype "passive"))
      (node (ref "S4") (pin "1") (pinfunction "1_1") (pintype "passive"))
      (node (ref "U$1") (pin "STBY") (pinfunction "STBY_STBY") (pintype "bidirectional"))
      (node (ref "U$1") (pin "VSS") (pinfunction "VSS_VSS") (pintype "bidirectional"))
      (node (ref "U$2") (pin "AGND") (pinfunction "AGND_AGND") (pintype "power_in"))
      (node (ref "U$2") (pin "GND") (pinfunction "GND_GND") (pintype "power_in"))
      (node (ref "U$3") (pin "3") (pinfunction "G1_3") (pintype "bidirectional"))
      (node (ref "U$3") (pin "8") (pinfunction "G2_8") (pintype "bidirectional"))
      (node (ref "U1") (pin "P$1") (pinfunction "VSS_P$1") (pintype "bidirectional"))
      (node (ref "U2") (pin "P$1") (pinfunction "VSS_P$1") (pintype "bidirectional"))
      (node (ref "U3") (pin "1") (pinfunction "PGND_1") (pintype "bidirectional"))
      (node (ref "U3") (pin "3") (pinfunction "AGND_3") (pintype "bidirectional"))
      (node (ref "U4") (pin "10") (pinfunction "~{SRCLR}_10") (pintype "input"))
      (node (ref "U4") (pin "13") (pinfunction "~{OE}_13") (pintype "input"))
      (node (ref "U4") (pin "8") (pinfunction "GND_8") (pintype "passive"))
    )
    (net (code "56") (name "Net-(C11-1)") (class "Default")
      (node (ref "C11") (pin "P$1") (pinfunction "1_P$1") (pintype "passive"))
      (node (ref "R12") (pin "2") (pinfunction "2_2") (pintype "passive"))
    )
    (net (code "57") (name "Net-(C11-2)") (class "Default")
      (node (ref "C11") (pin "P$2") (pinfunction "2_P$2") (pintype "passive"))
      (node (ref "U3") (pin "5") (pinfunction "COMP_5") (pintype "bidirectional"))
    )
    (net (code "58") (name "Net-(C23-1)") (class "Default")
      (node (ref "C23") (pin "P$1") (pinfunction "1_P$1") (pintype "passive"))
      (node (ref "R13") (pin "1") (pinfunction "1_1") (pintype "passive"))
      (node (ref "R14") (pin "2") (pinfunction "2_2") (pintype "passive"))
      (node (ref "U3") (pin "4") (pinfunction "FB_4") (pintype "bidirectional"))
    )
    (net (code "59") (name "Net-(D1-DO)") (class "Default")
      (node (ref "D1") (pin "2") (pinfunction "DO_2") (pintype "bidirectional"))
      (node (ref "D7") (pin "4") (pinfunction "DI_4") (pintype "bidirectional"))
    )
    (net (code "60") (name "Net-(D2-DI)") (class "Default")
      (node (ref "D2") (pin "4") (pinfunction "DI_4") (pintype "bidirectional"))
      (node (ref "D8") (pin "2") (pinfunction "DO_2") (pintype "bidirectional"))
    )
    (net (code "61") (name "Net-(D2-DO)") (class "Default")
      (node (ref "D2") (pin "2") (pinfunction "DO_2") (pintype "bidirectional"))
      (node (ref "D4") (pin "4") (pinfunction "DI_4") (pintype "bidirectional"))
    )
    (net (code "62") (name "Net-(D3-PadA)") (class "Default")
      (node (ref "D3") (pin "A") (pinfunction "A_A") (pintype "passive"))
      (node (ref "R15") (pin "1") (pinfunction "1_1") (pintype "passive"))
    )
    (net (code "63") (name "Net-(D4-DO)") (class "Default")
      (node (ref "D4") (pin "2") (pinfunction "DO_2") (pintype "bidirectional"))
      (node (ref "D6") (pin "4") (pinfunction "DI_4") (pintype "bidirectional"))
    )
    (net (code "64") (name "Net-(D5-C)") (class "Default")
      (node (ref "D5") (pin "K") (pinfunction "C_K") (pintype "passive"))
      (node (ref "R16") (pin "1") (pinfunction "1_1") (pintype "passive"))
    )
    (net (code "65") (name "Net-(D7-DO)") (class "Default")
      (node (ref "D7") (pin "2") (pinfunction "DO_2") (pintype "bidirectional"))
      (node (ref "D8") (pin "4") (pinfunction "DI_4") (pintype "bidirectional"))
    )
    (net (code "66") (name "Net-(D9-C)") (class "Default")
      (node (ref "D9") (pin "K") (pinfunction "C_K") (pintype "passive"))
      (node (ref "R17") (pin "1") (pinfunction "1_1") (pintype "passive"))
    )
    (net (code "67") (name "Net-(D10-PadC)") (class "Default")
      (node (ref "D10") (pin "C") (pinfunction "C_C") (pintype "passive"))
      (node (ref "R10") (pin "1") (pinfunction "1_1") (pintype "passive"))
      (node (ref "R11") (pin "1") (pinfunction "1_1") (pintype "passive"))
    )
    (net (code "68") (name "Net-(D11-DO)") (class "Default")
      (node (ref "D11") (pin "2") (pinfunction "DO_2") (pintype "bidirectional"))
      (node (ref "D12") (pin "4") (pinfunction "DI_4") (pintype "bidirectional"))
    )
    (net (code "69") (name "Net-(D12-DO)") (class "Default")
      (node (ref "D12") (pin "2") (pinfunction "DO_2") (pintype "bidirectional"))
      (node (ref "D13") (pin "4") (pinfunction "DI_4") (pintype "bidirectional"))
    )
    (net (code "70") (name "Net-(D13-DO)") (class "Default")
      (node (ref "D13") (pin "2") (pinfunction "DO_2") (pintype "bidirectional"))
      (node (ref "D14") (pin "4") (pinfunction "DI_4") (pintype "bidirectional"))
    )
    (net (code "71") (name "Net-(D14-DO)") (class "Default")
      (node (ref "D14") (pin "2") (pinfunction "DO_2") (pintype "bidirectional"))
      (node (ref "D15") (pin "4") (pinfunction "DI_4") (pintype "bidirectional"))
    )
    (net (code "72") (name "Net-(D15-DO)") (class "Default")
      (node (ref "D15") (pin "2") (pinfunction "DO_2") (pintype "bidirectional"))
      (node (ref "D16") (pin "4") (pinfunction "DI_4") (pintype "bidirectional"))
    )
    (net (code "73") (name "Net-(D16-DO)") (class "Default")
      (node (ref "D16") (pin "2") (pinfunction "DO_2") (pintype "bidirectional"))
      (node (ref "D17") (pin "4") (pinfunction "DI_4") (pintype "bidirectional"))
    )
    (net (code "74") (name "Net-(D17-DO)") (class "Default")
      (node (ref "D17") (pin "2") (pinfunction "DO_2") (pintype "bidirectional"))
      (node (ref "D18") (pin "4") (pinfunction "DI_4") (pintype "bidirectional"))
    )
    (net (code "75") (name "Net-(D18-DO)") (class "Default")
      (node (ref "D18") (pin "2") (pinfunction "DO_2") (pintype "bidirectional"))
      (node (ref "D19") (pin "4") (pinfunction "DI_4") (pintype "bidirectional"))
    )
    (net (code "76") (name "Net-(L1-1)") (class "Default")
      (node (ref "L1") (pin "P$1") (pinfunction "1_P$1") (pintype "passive"))
      (node (ref "U3") (pin "8") (pinfunction "VSW_8") (pintype "bidirectional"))
    )
    (net (code "77") (name "Net-(U4-QA)") (class "Default")
      (node (ref "R9") (pin "1") (pinfunction "1_1") (pintype "passive"))
      (node (ref "U4") (pin "15") (pinfunction "QA_15") (pintype "output"))
    )
    (net (code "78") (name "Net-(U4-QB)") (class "Default")
      (node (ref "R8") (pin "1") (pinfunction "1_1") (pintype "passive"))
      (node (ref "U4") (pin "1") (pinfunction "QB_1") (pintype "output"))
    )
    (net (code "79") (name "Net-(U4-QC)") (class "Default")
      (node (ref "R18") (pin "1") (pinfunction "1_1") (pintype "passive"))
      (node (ref "U4") (pin "2") (pinfunction "QC_2") (pintype "output"))
    )
    (net (code "80") (name "Net-(U4-QD)") (class "Default")
      (node (ref "R19") (pin "1") (pinfunction "1_1") (pintype "passive"))
      (node (ref "U4") (pin "3") (pinfunction "QD_3") (pintype "output"))
    )
    (net (code "81") (name "Net-(U4-QE)") (class "Default")
      (node (ref "R20") (pin "1") (pinfunction "1_1") (pintype "passive"))
      (node (ref "U4") (pin "4") (pinfunction "QE_4") (pintype "output"))
    )
    (net (code "82") (name "Net-(U4-QF)") (class "Default")
      (node (ref "R21") (pin "1") (pinfunction "1_1") (pintype "passive"))
      (node (ref "U4") (pin "5") (pinfunction "QF_5") (pintype "output"))
    )
    (net (code "83") (name "Net-(U4-QG)") (class "Default")
      (node (ref "R22") (pin "1") (pinfunction "1_1") (pintype "passive"))
      (node (ref "U4") (pin "6") (pinfunction "QG_6") (pintype "output"))
    )
    (net (code "84") (name "VIN") (class "Default")
      (node (ref "C1") (pin "P$1") (pinfunction "1_P$1") (pintype "passive"))
      (node (ref "C10") (pin "P$1") (pinfunction "1_P$1") (pintype "passive"))
      (node (ref "C12") (pin "P$1") (pinfunction "1_P$1") (pintype "passive"))
      (node (ref "C14") (pin "P$1") (pinfunction "1_P$1") (pintype "passive"))
      (node (ref "C15") (pin "P$1") (pinfunction "1_P$1") (pintype "passive"))
      (node (ref "C16") (pin "P$1") (pinfunction "1_P$1") (pintype "passive"))
      (node (ref "C17") (pin "P$1") (pinfunction "1_P$1") (pintype "passive"))
      (node (ref "C18") (pin "P$1") (pinfunction "1_P$1") (pintype "passive"))
      (node (ref "C19") (pin "P$1") (pinfunction "1_P$1") (pintype "passive"))
      (node (ref "C2") (pin "P$1") (pinfunction "1_P$1") (pintype "passive"))
      (node (ref "C21") (pin "P$1") (pinfunction "1_P$1") (pintype "passive"))
      (node (ref "C23") (pin "P$2") (pinfunction "2_P$2") (pintype "passive"))
      (node (ref "C3") (pin "P$1") (pinfunction "1_P$1") (pintype "passive"))
      (node (ref "C4") (pin "P$1") (pinfunction "1_P$1") (pintype "passive"))
      (node (ref "C5") (pin "P$1") (pinfunction "1_P$1") (pintype "passive"))
      (node (ref "C6") (pin "P$1") (pinfunction "1_P$1") (pintype "passive"))
      (node (ref "C7") (pin "P$1") (pinfunction "1_P$1") (pintype "passive"))
      (node (ref "C8") (pin "P$1") (pinfunction "1_P$1") (pintype "passive"))
      (node (ref "C9") (pin "P$1") (pinfunction "1_P$1") (pintype "passive"))
      (node (ref "D1") (pin "1") (pinfunction "VDD_1") (pintype "bidirectional"))
      (node (ref "D11") (pin "1") (pinfunction "VDD_1") (pintype "bidirectional"))
      (node (ref "D12") (pin "1") (pinfunction "VDD_1") (pintype "bidirectional"))
      (node (ref "D13") (pin "1") (pinfunction "VDD_1") (pintype "bidirectional"))
      (node (ref "D14") (pin "1") (pinfunction "VDD_1") (pintype "bidirectional"))
      (node (ref "D15") (pin "1") (pinfunction "VDD_1") (pintype "bidirectional"))
      (node (ref "D16") (pin "1") (pinfunction "VDD_1") (pintype "bidirectional"))
      (node (ref "D17") (pin "1") (pinfunction "VDD_1") (pintype "bidirectional"))
      (node (ref "D18") (pin "1") (pinfunction "VDD_1") (pintype "bidirectional"))
      (node (ref "D19") (pin "1") (pinfunction "VDD_1") (pintype "bidirectional"))
      (node (ref "D2") (pin "1") (pinfunction "VDD_1") (pintype "bidirectional"))
      (node (ref "D4") (pin "1") (pinfunction "VDD_1") (pintype "bidirectional"))
      (node (ref "D6") (pin "1") (pinfunction "VDD_1") (pintype "bidirectional"))
      (node (ref "D7") (pin "1") (pinfunction "VDD_1") (pintype "bidirectional"))
      (node (ref "D8") (pin "1") (pinfunction "VDD_1") (pintype "bidirectional"))
      (node (ref "J2") (pin "2") (pinfunction "2_2") (pintype "passive"))
      (node (ref "L1") (pin "P$2") (pinfunction "2_P$2") (pintype "passive"))
      (node (ref "R13") (pin "2") (pinfunction "2_2") (pintype "passive"))
      (node (ref "R23") (pin "2") (pinfunction "2_2") (pintype "passive"))
      (node (ref "R24") (pin "2") (pinfunction "2_2") (pintype "passive"))
      (node (ref "U$1") (pin "VDD") (pinfunction "VDD_VDD") (pintype "bidirectional"))
      (node (ref "U$2") (pin "VIN") (pinfunction "VIN_VIN") (pintype "power_in"))
      (node (ref "U1") (pin "P$28") (pinfunction "VDD_P$28") (pintype "bidirectional"))
      (node (ref "U2") (pin "P$28") (pinfunction "VDD_P$28") (pintype "bidirectional"))
      (node (ref "U4") (pin "16") (pinfunction "VCC_16") (pintype "power_in"))
    )
    (net (code "85") (name "unconnected-(D6-DO-Pad2)") (class "Default")
      (node (ref "D6") (pin "2") (pinfunction "DO_2") (pintype "bidirectional"))
    )
    (net (code "86") (name "unconnected-(D19-DO-Pad2)") (class "Default")
      (node (ref "D19") (pin "2") (pinfunction "DO_2") (pintype "bidirectional"))
    )
    (net (code "87") (name "unconnected-(LED1-APOS-A-Pad10)") (class "Default")
      (node (ref "LED1") (pin "10") (pinfunction "APOS-A_10") (pintype "bidirectional"))
    )
    (net (code "88") (name "unconnected-(LED1-APOS-C-Pad9)") (class "Default")
      (node (ref "LED1") (pin "9") (pinfunction "APOS-C_9") (pintype "bidirectional"))
    )
    (net (code "89") (name "unconnected-(LED1-COL-A-Pad4)") (class "Default")
      (node (ref "LED1") (pin "4") (pinfunction "COL-A_4") (pintype "bidirectional"))
    )
    (net (code "90") (name "unconnected-(LED1-COL-C-Pad12)") (class "Default")
      (node (ref "LED1") (pin "12") (pinfunction "COL-C_12") (pintype "bidirectional"))
    )
    (net (code "91") (name "unconnected-(LED2-APOS-A-Pad10)") (class "Default")
      (node (ref "LED2") (pin "10") (pinfunction "APOS-A_10") (pintype "bidirectional"))
    )
    (net (code "92") (name "unconnected-(LED2-APOS-C-Pad9)") (class "Default")
      (node (ref "LED2") (pin "9") (pinfunction "APOS-C_9") (pintype "bidirectional"))
    )
    (net (code "93") (name "unconnected-(LED2-COL-A-Pad4)") (class "Default")
      (node (ref "LED2") (pin "4") (pinfunction "COL-A_4") (pintype "bidirectional"))
    )
    (net (code "94") (name "unconnected-(LED2-COL-C-Pad12)") (class "Default")
      (node (ref "LED2") (pin "12") (pinfunction "COL-C_12") (pintype "bidirectional"))
    )
    (net (code "95") (name "unconnected-(U$2-0{slash}RX1{slash}T-Pad0)") (class "Default")
      (node (ref "U$2") (pin "0") (pinfunction "0/RX1/T_0") (pintype "bidirectional"))
    )
    (net (code "96") (name "unconnected-(U$2-1{slash}TX1{slash}T-Pad1)") (class "Default")
      (node (ref "U$2") (pin "1") (pinfunction "1/TX1/T_1") (pintype "bidirectional"))
    )
    (net (code "97") (name "unconnected-(U$2-7{slash}RX3-Pad7)") (class "Default")
      (node (ref "U$2") (pin "7") (pinfunction "7/RX3_7") (pintype "bidirectional"))
    )
    (net (code "98") (name "unconnected-(U$2-8{slash}TX3-Pad8)") (class "Default")
      (node (ref "U$2") (pin "8") (pinfunction "8/TX3_8") (pintype "bidirectional"))
    )
    (net (code "99") (name "unconnected-(U$2-12{slash}MISO-Pad12)") (class "Default")
      (node (ref "U$2") (pin "12") (pinfunction "12/MISO_12") (pintype "bidirectional"))
    )
    (net (code "100") (name "unconnected-(U$2-14{slash}A1-Pad14{slash}A0)") (class "Default")
      (node (ref "U$2") (pin "14/A0") (pinfunction "14/A1_14/A0") (pintype "bidirectional"))
    )
    (net (code "101") (name "unconnected-(U$2-15{slash}A1{slash}T-Pad15{slash}A1)") (class "Default")
      (node (ref "U$2") (pin "15/A1") (pinfunction "15/A1/T_15/A1") (pintype "bidirectional"))
    )
    (net (code "102") (name "unconnected-(U$2-16{slash}A2{slash}T-Pad16{slash}A2)") (class "Default")
      (node (ref "U$2") (pin "16/A2") (pinfunction "16/A2/T_16/A2") (pintype "bidirectional"))
    )
    (net (code "103") (name "unconnected-(U$2-17{slash}A3{slash}T-Pad17{slash}A3)") (class "Default")
      (node (ref "U$2") (pin "17/A3") (pinfunction "17/A3/T_17/A3") (pintype "bidirectional"))
    )
    (net (code "104") (name "unconnected-(U$2-18{slash}A4{slash}T{slash}SDA0-Pad18{slash}A4)") (class "Default")
      (node (ref "U$2") (pin "18/A4") (pinfunction "18/A4/T/SDA0_18/A4") (pintype "bidirectional"))
    )
    (net (code "105") (name "unconnected-(U$2-19{slash}A5{slash}T{slash}SCL0-Pad19{slash}A5)") (class "Default")
      (node (ref "U$2") (pin "19/A5") (pinfunction "19/A5/T/SCL0_19/A5") (pintype "bidirectional"))
    )
    (net (code "106") (name "unconnected-(U$3-DP-Pad5)") (class "Default")
      (node (ref "U$3") (pin "5") (pinfunction "DP_5") (pintype "bidirectional"))
    )
    (net (code "107") (name "unconnected-(U1-COM4-PadP$6)") (class "Default")
      (node (ref "U1") (pin "P$6") (pinfunction "COM4_P$6") (pintype "bidirectional"))
    )
    (net (code "108") (name "unconnected-(U1-COM5-PadP$7)") (class "Default")
      (node (ref "U1") (pin "P$7") (pinfunction "COM5_P$7") (pintype "bidirectional"))
    )
    (net (code "109") (name "unconnected-(U1-COM6-PadP$8)") (class "Default")
      (node (ref "U1") (pin "P$8") (pinfunction "COM6_P$8") (pintype "bidirectional"))
    )
    (net (code "110") (name "unconnected-(U1-COM7-PadP$9)") (class "Default")
      (node (ref "U1") (pin "P$9") (pinfunction "COM7_P$9") (pintype "bidirectional"))
    )
    (net (code "111") (name "unconnected-(U1-ROW8{slash}K6-PadP$17)") (class "Default")
      (node (ref "U1") (pin "P$17") (pinfunction "ROW8/K6_P$17") (pintype "bidirectional"))
    )
    (net (code "112") (name "unconnected-(U1-ROW9{slash}K7-PadP$16)") (class "Default")
      (node (ref "U1") (pin "P$16") (pinfunction "ROW9/K7_P$16") (pintype "bidirectional"))
    )
    (net (code "113") (name "unconnected-(U1-ROW10{slash}K8-PadP$15)") (class "Default")
      (node (ref "U1") (pin "P$15") (pinfunction "ROW10/K8_P$15") (pintype "bidirectional"))
    )
    (net (code "114") (name "unconnected-(U1-ROW11{slash}K9-PadP$14)") (class "Default")
      (node (ref "U1") (pin "P$14") (pinfunction "ROW11/K9_P$14") (pintype "bidirectional"))
    )
    (net (code "115") (name "unconnected-(U1-ROW12{slash}K10-PadP$13)") (class "Default")
      (node (ref "U1") (pin "P$13") (pinfunction "ROW12/K10_P$13") (pintype "bidirectional"))
    )
    (net (code "116") (name "unconnected-(U1-ROW13{slash}K11-PadP$12)") (class "Default")
      (node (ref "U1") (pin "P$12") (pinfunction "ROW13/K11_P$12") (pintype "bidirectional"))
    )
    (net (code "117") (name "unconnected-(U1-ROW14{slash}K12-PadP$11)") (class "Default")
      (node (ref "U1") (pin "P$11") (pinfunction "ROW14/K12_P$11") (pintype "bidirectional"))
    )
    (net (code "118") (name "unconnected-(U1-ROW15{slash}K13{slash}INT-PadP$10)") (class "Default")
      (node (ref "U1") (pin "P$10") (pinfunction "ROW15/K13/INT_P$10") (pintype "bidirectional"))
    )
    (net (code "119") (name "unconnected-(U2-COM4-PadP$6)") (class "Default")
      (node (ref "U2") (pin "P$6") (pinfunction "COM4_P$6") (pintype "bidirectional"))
    )
    (net (code "120") (name "unconnected-(U2-COM5-PadP$7)") (class "Default")
      (node (ref "U2") (pin "P$7") (pinfunction "COM5_P$7") (pintype "bidirectional"))
    )
    (net (code "121") (name "unconnected-(U2-COM6-PadP$8)") (class "Default")
      (node (ref "U2") (pin "P$8") (pinfunction "COM6_P$8") (pintype "bidirectional"))
    )
    (net (code "122") (name "unconnected-(U2-COM7-PadP$9)") (class "Default")
      (node (ref "U2") (pin "P$9") (pinfunction "COM7_P$9") (pintype "bidirectional"))
    )
    (net (code "123") (name "unconnected-(U2-ROW8{slash}K6-PadP$17)") (class "Default")
      (node (ref "U2") (pin "P$17") (pinfunction "ROW8/K6_P$17") (pintype "bidirectional"))
    )
    (net (code "124") (name "unconnected-(U2-ROW9{slash}K7-PadP$16)") (class "Default")
      (node (ref "U2") (pin "P$16") (pinfunction "ROW9/K7_P$16") (pintype "bidirectional"))
    )
    (net (code "125") (name "unconnected-(U2-ROW10{slash}K8-PadP$15)") (class "Default")
      (node (ref "U2") (pin "P$15") (pinfunction "ROW10/K8_P$15") (pintype "bidirectional"))
    )
    (net (code "126") (name "unconnected-(U2-ROW11{slash}K9-PadP$14)") (class "Default")
      (node (ref "U2") (pin "P$14") (pinfunction "ROW11/K9_P$14") (pintype "bidirectional"))
    )
    (net (code "127") (name "unconnected-(U2-ROW12{slash}K10-PadP$13)") (class "Default")
      (node (ref "U2") (pin "P$13") (pinfunction "ROW12/K10_P$13") (pintype "bidirectional"))
    )
    (net (code "128") (name "unconnected-(U2-ROW13{slash}K11-PadP$12)") (class "Default")
      (node (ref "U2") (pin "P$12") (pinfunction "ROW13/K11_P$12") (pintype "bidirectional"))
    )
    (net (code "129") (name "unconnected-(U2-ROW14{slash}K12-PadP$11)") (class "Default")
      (node (ref "U2") (pin "P$11") (pinfunction "ROW14/K12_P$11") (pintype "bidirectional"))
    )
    (net (code "130") (name "unconnected-(U2-ROW15{slash}K13{slash}INT-PadP$10)") (class "Default")
      (node (ref "U2") (pin "P$10") (pinfunction "ROW15/K13/INT_P$10") (pintype "bidirectional"))
    )
    (net (code "131") (name "unconnected-(U3-EN-Pad6)") (class "Default")
      (node (ref "U3") (pin "6") (pinfunction "EN_6") (pintype "bidirectional"))
    )
    (net (code "132") (name "unconnected-(U3-PG-Pad7)") (class "Default")
      (node (ref "U3") (pin "7") (pinfunction "PG_7") (pintype "bidirectional"))
    )
    (net (code "133") (name "unconnected-(U4-QH-Pad7)") (class "Default")
      (node (ref "U4") (pin "7") (pinfunction "QH_7") (pintype "output"))
    )
    (net (code "134") (name "unconnected-(U4-QH_2-Pad9)") (class "Default")
      (node (ref "U4") (pin "9") (pinfunction "QH_2_9") (pintype "output"))
    )
  )
)
